# LORA.net
KiCad netlist of a schematic drawn in Altium Designer
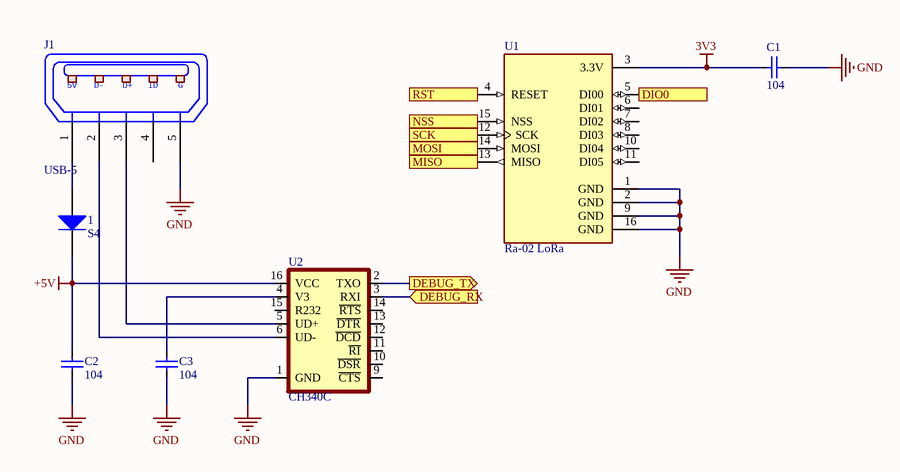
[diagram p0: LORA.SchDoc]

(export (version "E")
  (design (tool "Eeschema 10.0.6"))
  (components
    (comp (ref "1")
      (value "S4")
      (footprint "DIO-214AC(SMA)")
      (description "Dán")
      (libsource (lib "THU VIEN SCH") (part "Diode S4"))
    )
    (comp (ref "C1")
      (value "104")
      (footprint "CAP_0805")
      (description "Capacitor")
      (fields (field (name "PUBLISHER") "Altium Limited"))
      (libsource (lib "My Library") (part "CapSMD"))
    )
    (comp (ref "C2")
      (value "104")
      (footprint "CAP_0805")
      (description "Capacitor")
      (fields (field (name "PUBLISHER") "Altium Limited"))
      (libsource (lib "My Library") (part "CapSMD"))
    )
    (comp (ref "C3")
      (value "104")
      (footprint "CAP_0805")
      (description "Capacitor")
      (fields (field (name "PUBLISHER") "Altium Limited"))
      (libsource (lib "My Library") (part "CapSMD"))
    )
    (comp (ref "J1")
      (value "USB-5")
      (footprint "USB-M1")
      (fields
        (field (name "MANUFACTURER") "FCI")
        (field (name "MANUFACTURER PART NUMBER") "10118193-0001LF")
        (field (name ".CREATOR") "MM")
        (field (name ".CHECKED PCB") "RF")
        (field (name ".CHECKED SCH") "MM")
      )
      (libsource (lib "My Library") (part "USB-5"))
    )
    (comp (ref "U1")
      (value "Ra-02 LoRa")
      (footprint "Ra-02")
      (description "LoRa Module Ra-02")
      (libsource (lib "My Library") (part "Ra-02 LoRa"))
    )
    (comp (ref "U2")
      (value "CH340C")
      (footprint "SOP-16")
      (description "USB to serial chip CH340")
      (fields (field (name "MF") "WCH"))
      (libsource (lib "My Library") (part "CH340C"))
    )
  )
  (nets
    (net (code "1") (name "+5V") (class "Default")
      (node (ref "1") (pin "2") (pinfunction "K_2") (pintype "passive"))
      (node (ref "C2") (pin "2") (pinfunction "2_2") (pintype "passive"))
      (node (ref "U2") (pin "16") (pinfunction "VCC_16") (pintype "bidirectional"))
    )
    (net (code "2") (name "/DEBUG_RX") (class "Default")
      (node (ref "U2") (pin "3") (pinfunction "RXI_3") (pintype "bidirectional"))
    )
    (net (code "3") (name "/DEBUG_TX") (class "Default")
      (node (ref "U2") (pin "2") (pinfunction "TXO_2") (pintype "bidirectional"))
    )
    (net (code "4") (name "/DIO0") (class "Default")
      (node (ref "U1") (pin "5") (pinfunction "DI00_5") (pintype "bidirectional"))
    )
    (net (code "5") (name "/MISO") (class "Default")
      (node (ref "U1") (pin "13") (pinfunction "MISO_13") (pintype "output"))
    )
    (net (code "6") (name "/MOSI") (class "Default")
      (node (ref "U1") (pin "14") (pinfunction "MOSI_14") (pintype "input"))
    )
    (net (code "7") (name "/NSS") (class "Default")
      (node (ref "U1") (pin "15") (pinfunction "NSS_15") (pintype "input"))
    )
    (net (code "8") (name "/RST") (class "Default")
      (node (ref "U1") (pin "4") (pinfunction "RESET_4") (pintype "input"))
    )
    (net (code "9") (name "/SCK") (class "Default")
      (node (ref "U1") (pin "12") (pinfunction "SCK_12") (pintype "input"))
    )
    (net (code "10") (name "3V3") (class "Default")
      (node (ref "C1") (pin "2") (pinfunction "2_2") (pintype "passive"))
      (node (ref "U1") (pin "3") (pinfunction "3.3V_3") (pintype "power_in"))
    )
    (net (code "11") (name "GND") (class "Default")
      (node (ref "C1") (pin "1") (pinfunction "1_1") (pintype "passive"))
      (node (ref "C2") (pin "1") (pinfunction "1_1") (pintype "passive"))
      (node (ref "C3") (pin "1") (pinfunction "1_1") (pintype "passive"))
      (node (ref "J1") (pin "5") (pinfunction "P5_5") (pintype "passive"))
      (node (ref "U1") (pin "1") (pinfunction "GND_1") (pintype "power_in"))
      (node (ref "U1") (pin "16") (pinfunction "GND_16") (pintype "power_in"))
      (node (ref "U1") (pin "2") (pinfunction "GND_2") (pintype "power_in"))
      (node (ref "U1") (pin "9") (pinfunction "GND_9") (pintype "power_in"))
      (node (ref "U2") (pin "1") (pinfunction "GND_1") (pintype "bidirectional"))
    )
    (net (code "12") (name "Net-(1-A)") (class "Default")
      (node (ref "1") (pin "1") (pinfunction "A_1") (pintype "passive"))
      (node (ref "J1") (pin "1") (pinfunction "P1_1") (pintype "passive"))
    )
    (net (code "13") (name "Net-(J1-P2)") (class "Default")
      (node (ref "J1") (pin "2") (pinfunction "P2_2") (pintype "passive"))
      (node (ref "U2") (pin "6") (pinfunction "UD-_6") (pintype "bidirectional"))
    )
    (net (code "14") (name "Net-(J1-P3)") (class "Default")
      (node (ref "J1") (pin "3") (pinfunction "P3_3") (pintype "passive"))
      (node (ref "U2") (pin "5") (pinfunction "UD+_5") (pintype "bidirectional"))
    )
    (net (code "15") (name "Net-(U2-V3)") (class "Default")
      (node (ref "C3") (pin "2") (pinfunction "2_2") (pintype "passive"))
      (node (ref "U2") (pin "4") (pinfunction "V3_4") (pintype "bidirectional"))
    )
    (net (code "16") (name "unconnected-(J1-P4-Pad4)") (class "Default")
      (node (ref "J1") (pin "4") (pinfunction "P4_4") (pintype "passive"))
    )
    (net (code "17") (name "unconnected-(U1-DI01-Pad6)") (class "Default")
      (node (ref "U1") (pin "6") (pinfunction "DI01_6") (pintype "bidirectional"))
    )
    (net (code "18") (name "unconnected-(U1-DI02-Pad7)") (class "Default")
      (node (ref "U1") (pin "7") (pinfunction "DI02_7") (pintype "bidirectional"))
    )
    (net (code "19") (name "unconnected-(U1-DI03-Pad8)") (class "Default")
      (node (ref "U1") (pin "8") (pinfunction "DI03_8") (pintype "bidirectional"))
    )
    (net (code "20") (name "unconnected-(U1-DI04-Pad10)") (class "Default")
      (node (ref "U1") (pin "10") (pinfunction "DI04_10") (pintype "bidirectional"))
    )
    (net (code "21") (name "unconnected-(U1-DI05-Pad11)") (class "Default")
      (node (ref "U1") (pin "11") (pinfunction "DI05_11") (pintype "bidirectional"))
    )
    (net (code "22") (name "unconnected-(U2-R232-Pad15)") (class "Default")
      (node (ref "U2") (pin "15") (pinfunction "R232_15") (pintype "bidirectional"))
    )
    (net (code "23") (name "unconnected-(U2-~{CTS}-Pad9)") (class "Default")
      (node (ref "U2") (pin "9") (pinfunction "~{CTS}_9") (pintype "bidirectional"))
    )
    (net (code "24") (name "unconnected-(U2-~{DCD}-Pad12)") (class "Default")
      (node (ref "U2") (pin "12") (pinfunction "~{DCD}_12") (pintype "bidirectional"))
    )
    (net (code "25") (name "unconnected-(U2-~{DSR}-Pad10)") (class "Default")
      (node (ref "U2") (pin "10") (pinfunction "~{DSR}_10") (pintype "bidirectional"))
    )
    (net (code "26") (name "unconnected-(U2-~{DTR}-Pad13)") (class "Default")
      (node (ref "U2") (pin "13") (pinfunction "~{DTR}_13") (pintype "bidirectional"))
    )
    (net (code "27") (name "unconnected-(U2-~{RI}-Pad11)") (class "Default")
      (node (ref "U2") (pin "11") (pinfunction "~{RI}_11") (pintype "bidirectional"))
    )
    (net (code "28") (name "unconnected-(U2-~{RTS}-Pad14)") (class "Default")
      (node (ref "U2") (pin "14") (pinfunction "~{RTS}_14") (pintype "bidirectional"))
    )
  )
)
